# SCH_Hackclubtut_2024-03-08.net
KiCad netlist of a schematic drawn in EasyEDA
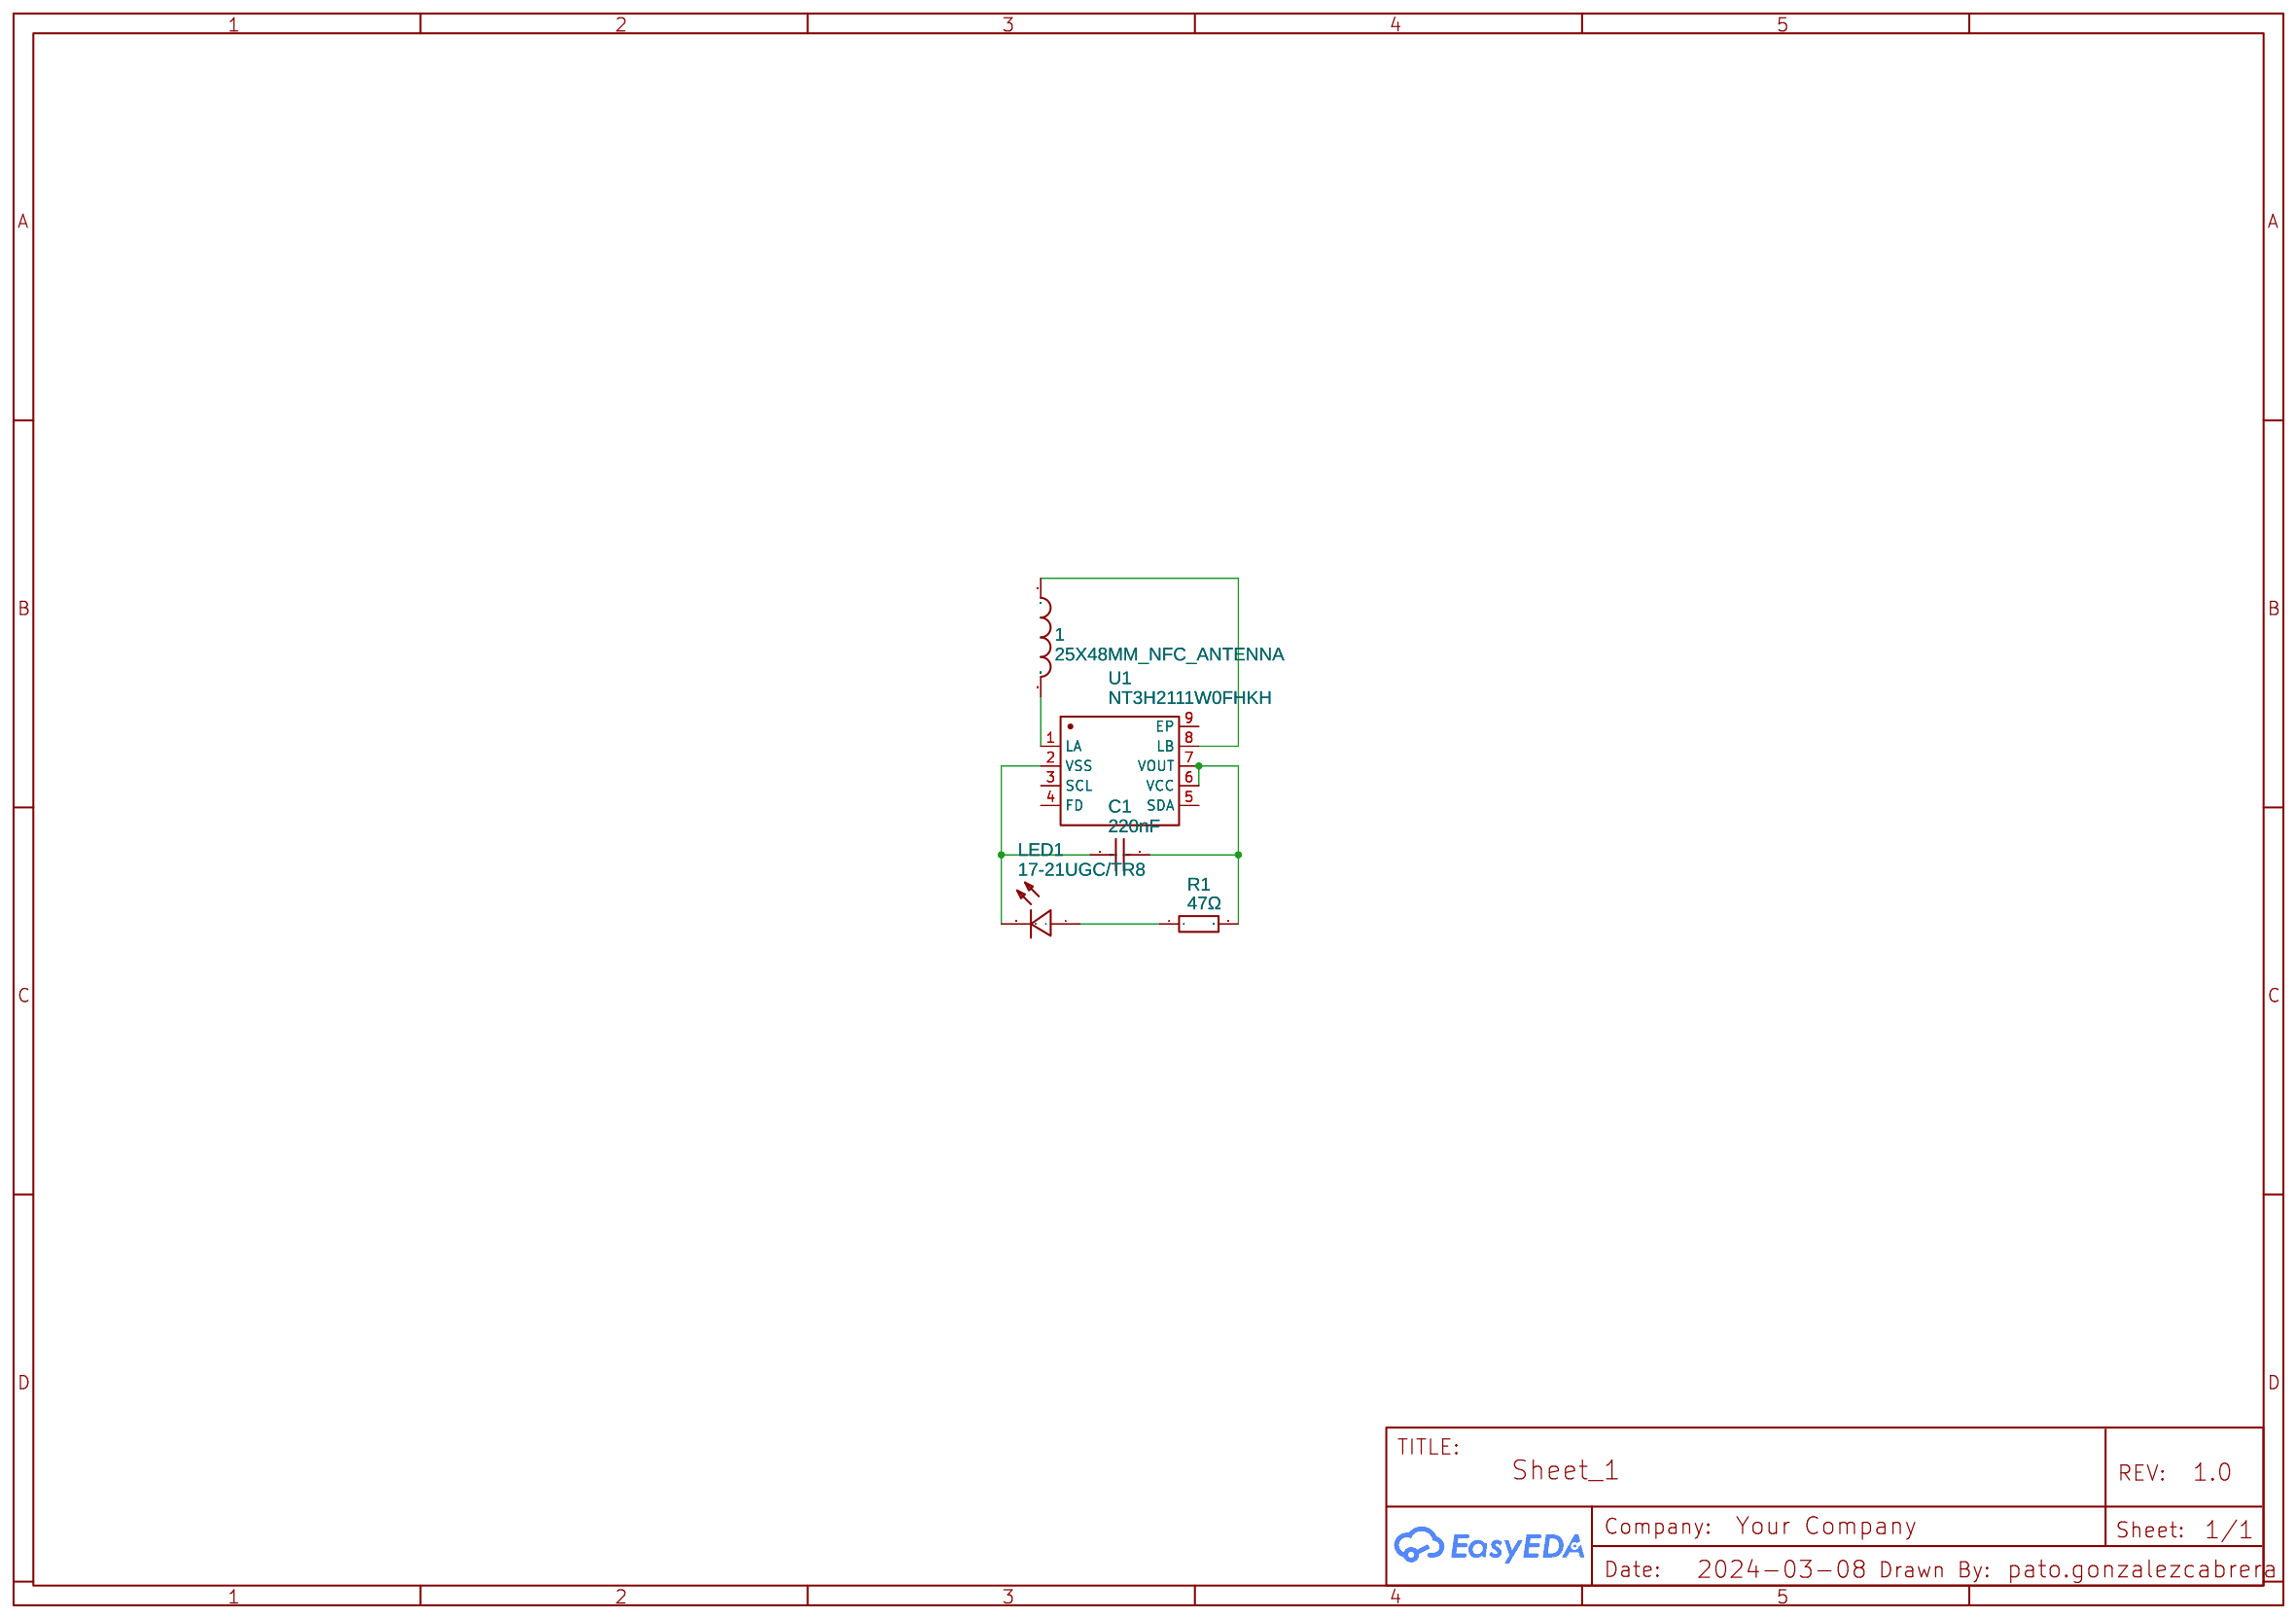
[diagram p0: schematic sheet]

(export (version "E")
  (design (tool "Eeschema 10.0.6"))
  (components
    (comp (ref "1") (value "25X48MM_NFC_ANTENNA") (libsource (lib "") (part "25X48MM_NFC_ANTENNA")))
    (comp (ref "C1")
      (value "220nF")
      (fields
        (field (name "Manufacturer Part") "CL10B224KA8NNNC")
        (field (name "Manufacturer") "SAMSUNG(三星)")
      )
      (libsource (lib "") (part "CL10B224KA8NNNC"))
    )
    (comp (ref "LED1")
      (value "17-21UGC/TR8")
      (fields (field (name "Manufacturer") "EVERLIGHT(亿光)"))
      (libsource (lib "") (part "17-21UGC/TR8"))
    )
    (comp (ref "R1")
      (value "47Ω")
      (fields
        (field (name "Manufacturer Part") "0603WAF470JT5E")
        (field (name "Manufacturer") "UNI-ROYAL(厚声)")
      )
      (libsource (lib "") (part "0603WAF470JT5E"))
    )
    (comp (ref "U1")
      (value "NT3H2111W0FHKH")
      (fields (field (name "Manufacturer") "NXP(恩智浦)"))
      (libsource (lib "") (part "NT3H2111W0FHKH"))
    )
  )
  (nets
    (net (code "1") (name "Net-(LED1-A)") (class "Default")
      (node (ref "LED1") (pin "1") (pinfunction "A_1") (pintype "unspecified"))
      (node (ref "R1") (pin "1") (pinfunction "1_1") (pintype "input"))
    )
    (net (code "2") (name "Net-(LED1-K)") (class "Default")
      (node (ref "C1") (pin "1") (pinfunction "1_1") (pintype "input"))
      (node (ref "LED1") (pin "2") (pinfunction "K_2") (pintype "unspecified"))
      (node (ref "U1") (pin "2") (pinfunction "VSS_2") (pintype "unspecified"))
    )
    (net (code "3") (name "Net-(U1-LA)") (class "Default")
      (node (ref "1") (pin "P$2") (pinfunction "P$2_P$2") (pintype "bidirectional"))
      (node (ref "U1") (pin "1") (pinfunction "LA_1") (pintype "unspecified"))
    )
    (net (code "4") (name "Net-(U1-LB)") (class "Default")
      (node (ref "1") (pin "P$1") (pinfunction "P$1_P$1") (pintype "bidirectional"))
      (node (ref "U1") (pin "8") (pinfunction "LB_8") (pintype "unspecified"))
    )
    (net (code "5") (name "Net-(U1-VCC)") (class "Default")
      (node (ref "C1") (pin "2") (pinfunction "2_2") (pintype "input"))
      (node (ref "R1") (pin "2") (pinfunction "2_2") (pintype "input"))
      (node (ref "U1") (pin "6") (pinfunction "VCC_6") (pintype "unspecified"))
      (node (ref "U1") (pin "7") (pinfunction "VOUT_7") (pintype "unspecified"))
    )
    (net (code "6") (name "unconnected-(U1-EP-Pad9)") (class "Default")
      (node (ref "U1") (pin "9") (pinfunction "EP_9") (pintype "unspecified"))
    )
    (net (code "7") (name "unconnected-(U1-FD-Pad4)") (class "Default")
      (node (ref "U1") (pin "4") (pinfunction "FD_4") (pintype "unspecified"))
    )
    (net (code "8") (name "unconnected-(U1-SCL-Pad3)") (class "Default")
      (node (ref "U1") (pin "3") (pinfunction "SCL_3") (pintype "unspecified"))
    )
    (net (code "9") (name "unconnected-(U1-SDA-Pad5)") (class "Default")
      (node (ref "U1") (pin "5") (pinfunction "SDA_5") (pintype "unspecified"))
    )
  )
)
